# dacBreakout.net
KiCad netlist of a schematic drawn in EAGLE
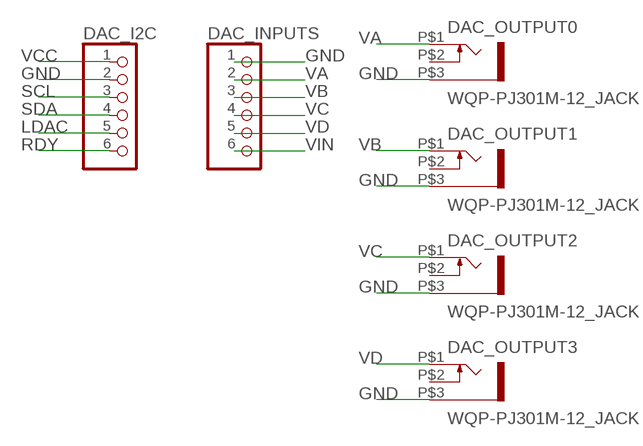
[diagram p0: schematic, sheet 1]

(export (version "E")
  (design (tool "Eeschema 10.0.6"))
  (components
    (comp (ref "DAC_I2C")
      (value "PINHD-1X6B")
      (footprint "eagle-import:1X06-BIG")
      (libsource (lib "eagle-import") (part "PINHD-1X6B"))
    )
    (comp (ref "DAC_INPUTS")
      (value "PINHD-1X6B")
      (footprint "eagle-import:1X06-BIG")
      (libsource (lib "eagle-import") (part "PINHD-1X6B"))
    )
    (comp (ref "DAC_OUTPUT0")
      (value "WQP-PJ301M-12_JACK")
      (footprint "eagle-import:WQP-PJ301M-12_JACK")
      (libsource (lib "eagle-import") (part "WQP-PJ301M-12_JACK"))
    )
    (comp (ref "DAC_OUTPUT1")
      (value "WQP-PJ301M-12_JACK")
      (footprint "eagle-import:WQP-PJ301M-12_JACK")
      (libsource (lib "eagle-import") (part "WQP-PJ301M-12_JACK"))
    )
    (comp (ref "DAC_OUTPUT2")
      (value "WQP-PJ301M-12_JACK")
      (footprint "eagle-import:WQP-PJ301M-12_JACK")
      (libsource (lib "eagle-import") (part "WQP-PJ301M-12_JACK"))
    )
    (comp (ref "DAC_OUTPUT3")
      (value "WQP-PJ301M-12_JACK")
      (footprint "eagle-import:WQP-PJ301M-12_JACK")
      (libsource (lib "eagle-import") (part "WQP-PJ301M-12_JACK"))
    )
  )
  (nets
    (net (code "1") (name "/GND") (class "Default")
      (node (ref "DAC_I2C") (pin "2") (pinfunction "2_2") (pintype "passive"))
      (node (ref "DAC_INPUTS") (pin "1") (pinfunction "1_1") (pintype "passive"))
      (node (ref "DAC_OUTPUT0") (pin "P$3") (pinfunction "1_P$3") (pintype "passive"))
      (node (ref "DAC_OUTPUT1") (pin "P$3") (pinfunction "1_P$3") (pintype "passive"))
      (node (ref "DAC_OUTPUT2") (pin "P$3") (pinfunction "1_P$3") (pintype "passive"))
      (node (ref "DAC_OUTPUT3") (pin "P$3") (pinfunction "1_P$3") (pintype "passive"))
    )
    (net (code "2") (name "/LDAC") (class "Default")
      (node (ref "DAC_I2C") (pin "5") (pinfunction "5_5") (pintype "passive"))
    )
    (net (code "3") (name "/RDY") (class "Default")
      (node (ref "DAC_I2C") (pin "6") (pinfunction "6_6") (pintype "passive"))
    )
    (net (code "4") (name "/SCL") (class "Default")
      (node (ref "DAC_I2C") (pin "3") (pinfunction "3_3") (pintype "passive"))
    )
    (net (code "5") (name "/SDA") (class "Default")
      (node (ref "DAC_I2C") (pin "4") (pinfunction "4_4") (pintype "passive"))
    )
    (net (code "6") (name "/VA") (class "Default")
      (node (ref "DAC_INPUTS") (pin "2") (pinfunction "2_2") (pintype "passive"))
      (node (ref "DAC_OUTPUT0") (pin "P$1") (pinfunction "2_P$1") (pintype "passive"))
    )
    (net (code "7") (name "/VB") (class "Default")
      (node (ref "DAC_INPUTS") (pin "3") (pinfunction "3_3") (pintype "passive"))
      (node (ref "DAC_OUTPUT1") (pin "P$1") (pinfunction "2_P$1") (pintype "passive"))
    )
    (net (code "8") (name "/VC") (class "Default")
      (node (ref "DAC_INPUTS") (pin "4") (pinfunction "4_4") (pintype "passive"))
      (node (ref "DAC_OUTPUT2") (pin "P$1") (pinfunction "2_P$1") (pintype "passive"))
    )
    (net (code "9") (name "/VCC") (class "Default")
      (node (ref "DAC_I2C") (pin "1") (pinfunction "1_1") (pintype "passive"))
    )
    (net (code "10") (name "/VD") (class "Default")
      (node (ref "DAC_INPUTS") (pin "5") (pinfunction "5_5") (pintype "passive"))
      (node (ref "DAC_OUTPUT3") (pin "P$1") (pinfunction "2_P$1") (pintype "passive"))
    )
    (net (code "11") (name "/VIN") (class "Default")
      (node (ref "DAC_INPUTS") (pin "6") (pinfunction "6_6") (pintype "passive"))
    )
    (net (code "12") (name "unconnected-(DAC_OUTPUT0-3-PadP$2)") (class "Default")
      (node (ref "DAC_OUTPUT0") (pin "P$2") (pinfunction "3_P$2") (pintype "passive"))
    )
    (net (code "13") (name "unconnected-(DAC_OUTPUT1-3-PadP$2)") (class "Default")
      (node (ref "DAC_OUTPUT1") (pin "P$2") (pinfunction "3_P$2") (pintype "passive"))
    )
    (net (code "14") (name "unconnected-(DAC_OUTPUT2-3-PadP$2)") (class "Default")
      (node (ref "DAC_OUTPUT2") (pin "P$2") (pinfunction "3_P$2") (pintype "passive"))
    )
    (net (code "15") (name "unconnected-(DAC_OUTPUT3-3-PadP$2)") (class "Default")
      (node (ref "DAC_OUTPUT3") (pin "P$2") (pinfunction "3_P$2") (pintype "passive"))
    )
  )
)
